# Mako_DSP_Audio_Codec.net
KiCad netlist of a schematic drawn in Altium Designer
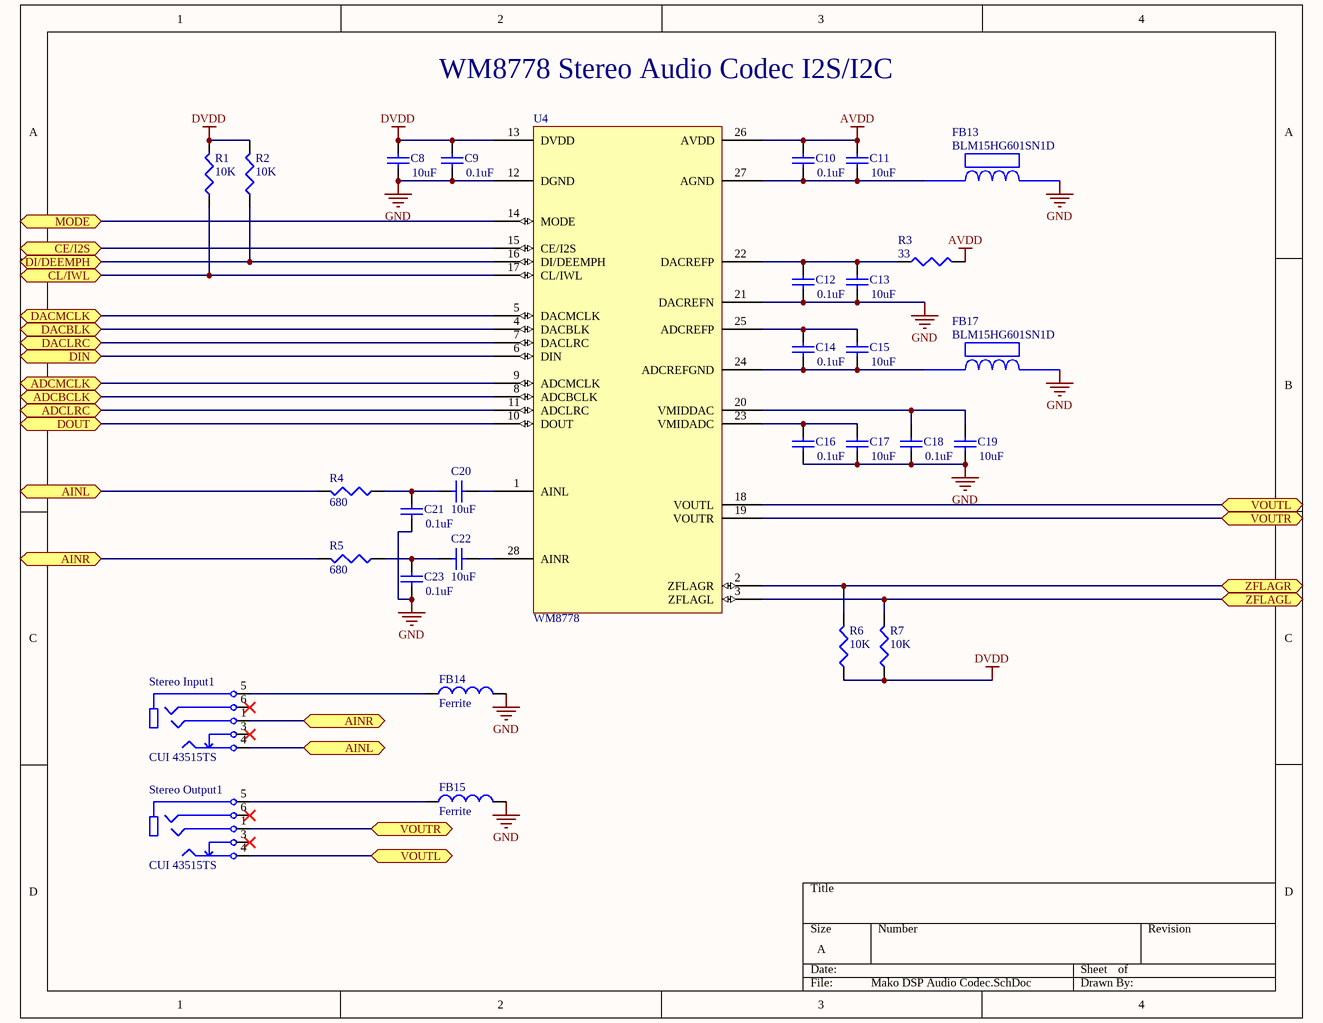
[diagram p0: Mako DSP Audio Codec.SchDoc]

(export (version "E")
  (design (tool "Eeschema 10.0.6"))
  (components
    (comp (ref "C8")
      (value "10uF")
      (footprint "1608[0603]")
      (description "Capacitor (Semiconductor SIM Model)")
      (fields (field (name "Comment") "Cap Semi") (field (name "PUBLISHER") "Altium Limited"))
      (libsource (lib "Miscellaneous Devices") (part "Cap Semi"))
    )
    (comp (ref "C9")
      (value "0.1uF")
      (footprint "1608[0603]")
      (description "Capacitor (Semiconductor SIM Model)")
      (fields (field (name "Comment") "Cap Semi") (field (name "PUBLISHER") "Altium Limited"))
      (libsource (lib "Miscellaneous Devices") (part "Cap Semi"))
    )
    (comp (ref "C10")
      (value "0.1uF")
      (footprint "1608[0603]")
      (description "Capacitor (Semiconductor SIM Model)")
      (fields (field (name "Comment") "Cap Semi") (field (name "PUBLISHER") "Altium Limited"))
      (libsource (lib "Miscellaneous Devices") (part "Cap Semi"))
    )
    (comp (ref "C11")
      (value "10uF")
      (footprint "1608[0603]")
      (description "Capacitor (Semiconductor SIM Model)")
      (fields (field (name "Comment") "Cap Semi") (field (name "PUBLISHER") "Altium Limited"))
      (libsource (lib "Miscellaneous Devices") (part "Cap Semi"))
    )
    (comp (ref "C12")
      (value "0.1uF")
      (footprint "1608[0603]")
      (description "Capacitor (Semiconductor SIM Model)")
      (fields (field (name "Comment") "Cap Semi") (field (name "PUBLISHER") "Altium Limited"))
      (libsource (lib "Miscellaneous Devices") (part "Cap Semi"))
    )
    (comp (ref "C13")
      (value "10uF")
      (footprint "1608[0603]")
      (description "Capacitor (Semiconductor SIM Model)")
      (fields (field (name "Comment") "Cap Semi") (field (name "PUBLISHER") "Altium Limited"))
      (libsource (lib "Miscellaneous Devices") (part "Cap Semi"))
    )
    (comp (ref "C14")
      (value "0.1uF")
      (footprint "1608[0603]")
      (description "Capacitor (Semiconductor SIM Model)")
      (fields (field (name "Comment") "Cap Semi") (field (name "PUBLISHER") "Altium Limited"))
      (libsource (lib "Miscellaneous Devices") (part "Cap Semi"))
    )
    (comp (ref "C15")
      (value "10uF")
      (footprint "1608[0603]")
      (description "Capacitor (Semiconductor SIM Model)")
      (fields (field (name "Comment") "Cap Semi") (field (name "PUBLISHER") "Altium Limited"))
      (libsource (lib "Miscellaneous Devices") (part "Cap Semi"))
    )
    (comp (ref "C16")
      (value "0.1uF")
      (footprint "1608[0603]")
      (description "Capacitor (Semiconductor SIM Model)")
      (fields (field (name "Comment") "Cap Semi") (field (name "PUBLISHER") "Altium Limited"))
      (libsource (lib "Miscellaneous Devices") (part "Cap Semi"))
    )
    (comp (ref "C17")
      (value "10uF")
      (footprint "1608[0603]")
      (description "Capacitor (Semiconductor SIM Model)")
      (fields (field (name "Comment") "Cap Semi") (field (name "PUBLISHER") "Altium Limited"))
      (libsource (lib "Miscellaneous Devices") (part "Cap Semi"))
    )
    (comp (ref "C18")
      (value "0.1uF")
      (footprint "1608[0603]")
      (description "Capacitor (Semiconductor SIM Model)")
      (fields (field (name "Comment") "Cap Semi") (field (name "PUBLISHER") "Altium Limited"))
      (libsource (lib "Miscellaneous Devices") (part "Cap Semi"))
    )
    (comp (ref "C19")
      (value "10uF")
      (footprint "1608[0603]")
      (description "Capacitor (Semiconductor SIM Model)")
      (fields (field (name "Comment") "Cap Semi") (field (name "PUBLISHER") "Altium Limited"))
      (libsource (lib "Miscellaneous Devices") (part "Cap Semi"))
    )
    (comp (ref "C20")
      (value "10uF")
      (footprint "Panasonic VS B")
      (description "Capacitor (Semiconductor SIM Model)")
      (fields (field (name "Comment") "Cap Semi") (field (name "PUBLISHER") "Altium Limited"))
      (libsource (lib "Miscellaneous Devices") (part "Cap Semi"))
    )
    (comp (ref "C21")
      (value "0.1uF")
      (footprint "SM 0805 - gap trimmed")
      (description "Capacitor (Semiconductor SIM Model)")
      (fields (field (name "Comment") "Cap Semi") (field (name "PUBLISHER") "Altium Limited"))
      (libsource (lib "Miscellaneous Devices") (part "Cap Semi"))
    )
    (comp (ref "C22")
      (value "10uF")
      (footprint "Panasonic VS B")
      (description "Capacitor (Semiconductor SIM Model)")
      (fields (field (name "Comment") "Cap Semi") (field (name "PUBLISHER") "Altium Limited"))
      (libsource (lib "Miscellaneous Devices") (part "Cap Semi"))
    )
    (comp (ref "C23")
      (value "0.1uF")
      (footprint "SM 0805 - gap trimmed")
      (description "Capacitor (Semiconductor SIM Model)")
      (fields (field (name "Comment") "Cap Semi") (field (name "PUBLISHER") "Altium Limited"))
      (libsource (lib "Miscellaneous Devices") (part "Cap Semi"))
    )
    (comp (ref "FB13")
      (value "BLM15HG601SN1D")
      (footprint "BLM18PG121SN1D")
      (libsource (lib "AHD Part Library") (part "BLM15HG601SN1D"))
    )
    (comp (ref "FB14")
      (value "Ferrite")
      (footprint "SM 0805 - gap trimmed")
      (description "Inductor")
      (fields (field (name "PUBLISHER") "Altium Limited"))
      (libsource (lib "Miscellaneous Devices") (part "Inductor"))
    )
    (comp (ref "FB15")
      (value "Ferrite")
      (footprint "SM 0805 - gap trimmed")
      (description "Inductor")
      (fields (field (name "PUBLISHER") "Altium Limited"))
      (libsource (lib "Miscellaneous Devices") (part "Inductor"))
    )
    (comp (ref "FB17")
      (value "BLM15HG601SN1D")
      (footprint "BLM18PG121SN1D")
      (libsource (lib "AHD Part Library") (part "BLM15HG601SN1D"))
    )
    (comp (ref "R1")
      (value "10K")
      (footprint "J1-0603")
      (description "Resistor")
      (fields (field (name "Comment") "Res3") (field (name "PUBLISHER") "Altium Limited"))
      (libsource (lib "Miscellaneous Devices") (part "Res3"))
    )
    (comp (ref "R2")
      (value "10K")
      (footprint "J1-0603")
      (description "Resistor")
      (fields (field (name "Comment") "Res3") (field (name "PUBLISHER") "Altium Limited"))
      (libsource (lib "Miscellaneous Devices") (part "Res3"))
    )
    (comp (ref "R3")
      (value "33")
      (footprint "J1-0603")
      (description "Resistor")
      (fields (field (name "Comment") "Res3") (field (name "PUBLISHER") "Altium Limited"))
      (libsource (lib "Miscellaneous Devices") (part "Res3"))
    )
    (comp (ref "R4")
      (value "680")
      (footprint "SM 0805 - gap trimmed")
      (description "Resistor")
      (fields (field (name "Comment") "Res3") (field (name "PUBLISHER") "Altium Limited"))
      (libsource (lib "Miscellaneous Devices") (part "Res3"))
    )
    (comp (ref "R5")
      (value "680")
      (footprint "SM 0805 - gap trimmed")
      (description "Resistor")
      (fields (field (name "Comment") "Res3") (field (name "PUBLISHER") "Altium Limited"))
      (libsource (lib "Miscellaneous Devices") (part "Res3"))
    )
    (comp (ref "R6")
      (value "10K")
      (footprint "J1-0603")
      (description "Resistor")
      (fields (field (name "Comment") "Res3") (field (name "PUBLISHER") "Altium Limited"))
      (libsource (lib "Miscellaneous Devices") (part "Res3"))
    )
    (comp (ref "R7")
      (value "10K")
      (footprint "J1-0603")
      (description "Resistor")
      (fields (field (name "Comment") "Res3") (field (name "PUBLISHER") "Altium Limited"))
      (libsource (lib "Miscellaneous Devices") (part "Res3"))
    )
    (comp (ref "Stereo Input1")
      (value "CUI 43515TS")
      (footprint "CUI SJ-43515TS")
      (libsource (lib "Adams Altium Library") (part "CUI 43515TS"))
    )
    (comp (ref "Stereo Output1")
      (value "CUI 43515TS")
      (footprint "CUI SJ-43515TS")
      (libsource (lib "Adams Altium Library") (part "CUI 43515TS"))
    )
    (comp (ref "U4")
      (value "WM8778")
      (footprint "WM8778")
      (libsource (lib "Mako DSP Schematic Library") (part "WM8778"))
    )
  )
  (nets
    (net (code "1") (name "/ADCBCLK") (class "Default")
      (node (ref "U4") (pin "8") (pinfunction "ADCBCLK_8") (pintype "bidirectional"))
    )
    (net (code "2") (name "/ADCLRC") (class "Default")
      (node (ref "U4") (pin "11") (pinfunction "ADCLRC_11") (pintype "bidirectional"))
    )
    (net (code "3") (name "/ADCMCLK") (class "Default")
      (node (ref "U4") (pin "9") (pinfunction "ADCMCLK_9") (pintype "bidirectional"))
    )
    (net (code "4") (name "/AINL") (class "Default")
      (node (ref "R4") (pin "2") (pinfunction "2_2") (pintype "passive"))
      (node (ref "Stereo Input1") (pin "4") (pinfunction "TIP_4") (pintype "passive"))
    )
    (net (code "5") (name "/AINR") (class "Default")
      (node (ref "R5") (pin "2") (pinfunction "2_2") (pintype "passive"))
      (node (ref "Stereo Input1") (pin "1") (pinfunction "R1_1") (pintype "passive"))
    )
    (net (code "6") (name "/CE{slash}I2S") (class "Default")
      (node (ref "U4") (pin "15") (pinfunction "CE/I2S_15") (pintype "bidirectional"))
    )
    (net (code "7") (name "/CL{slash}IWL") (class "Default")
      (node (ref "R1") (pin "1") (pinfunction "1_1") (pintype "passive"))
      (node (ref "U4") (pin "17") (pinfunction "CL/IWL_17") (pintype "bidirectional"))
    )
    (net (code "8") (name "/DACBLK") (class "Default")
      (node (ref "U4") (pin "4") (pinfunction "DACBLK_4") (pintype "bidirectional"))
    )
    (net (code "9") (name "/DACLRC") (class "Default")
      (node (ref "U4") (pin "7") (pinfunction "DACLRC_7") (pintype "bidirectional"))
    )
    (net (code "10") (name "/DACMCLK") (class "Default")
      (node (ref "U4") (pin "5") (pinfunction "DACMCLK_5") (pintype "bidirectional"))
    )
    (net (code "11") (name "/DIN") (class "Default")
      (node (ref "U4") (pin "6") (pinfunction "DIN_6") (pintype "bidirectional"))
    )
    (net (code "12") (name "/DI{slash}DEEMPH") (class "Default")
      (node (ref "R2") (pin "1") (pinfunction "1_1") (pintype "passive"))
      (node (ref "U4") (pin "16") (pinfunction "DI/DEEMPH_16") (pintype "bidirectional"))
    )
    (net (code "13") (name "/DOUT") (class "Default")
      (node (ref "U4") (pin "10") (pinfunction "DOUT_10") (pintype "bidirectional"))
    )
    (net (code "14") (name "/MODE") (class "Default")
      (node (ref "U4") (pin "14") (pinfunction "MODE_14") (pintype "bidirectional"))
    )
    (net (code "15") (name "/VOUTL") (class "Default")
      (node (ref "Stereo Output1") (pin "4") (pinfunction "TIP_4") (pintype "passive"))
      (node (ref "U4") (pin "18") (pinfunction "VOUTL_18") (pintype "passive"))
    )
    (net (code "16") (name "/VOUTR") (class "Default")
      (node (ref "Stereo Output1") (pin "1") (pinfunction "R1_1") (pintype "passive"))
      (node (ref "U4") (pin "19") (pinfunction "VOUTR_19") (pintype "passive"))
    )
    (net (code "17") (name "/ZFLAGL") (class "Default")
      (node (ref "R7") (pin "2") (pinfunction "2_2") (pintype "passive"))
      (node (ref "U4") (pin "3") (pinfunction "ZFLAGL_3") (pintype "bidirectional"))
    )
    (net (code "18") (name "/ZFLAGR") (class "Default")
      (node (ref "R6") (pin "2") (pinfunction "2_2") (pintype "passive"))
      (node (ref "U4") (pin "2") (pinfunction "ZFLAGR_2") (pintype "bidirectional"))
    )
    (net (code "19") (name "AVDD") (class "Default")
      (node (ref "C10") (pin "2") (pinfunction "2_2") (pintype "passive"))
      (node (ref "C11") (pin "2") (pinfunction "2_2") (pintype "passive"))
      (node (ref "R3") (pin "2") (pinfunction "2_2") (pintype "passive"))
      (node (ref "U4") (pin "26") (pinfunction "AVDD_26") (pintype "passive"))
    )
    (net (code "20") (name "DVDD") (class "Default")
      (node (ref "C8") (pin "2") (pinfunction "2_2") (pintype "passive"))
      (node (ref "C9") (pin "2") (pinfunction "2_2") (pintype "passive"))
      (node (ref "R1") (pin "2") (pinfunction "2_2") (pintype "passive"))
      (node (ref "R2") (pin "2") (pinfunction "2_2") (pintype "passive"))
      (node (ref "R6") (pin "1") (pinfunction "1_1") (pintype "passive"))
      (node (ref "R7") (pin "1") (pinfunction "1_1") (pintype "passive"))
      (node (ref "U4") (pin "13") (pinfunction "DVDD_13") (pintype "passive"))
    )
    (net (code "21") (name "GND") (class "Default")
      (node (ref "C12") (pin "1") (pinfunction "1_1") (pintype "passive"))
      (node (ref "C13") (pin "1") (pinfunction "1_1") (pintype "passive"))
      (node (ref "C16") (pin "1") (pinfunction "1_1") (pintype "passive"))
      (node (ref "C17") (pin "1") (pinfunction "1_1") (pintype "passive"))
      (node (ref "C18") (pin "1") (pinfunction "1_1") (pintype "passive"))
      (node (ref "C19") (pin "1") (pinfunction "1_1") (pintype "passive"))
      (node (ref "C21") (pin "1") (pinfunction "1_1") (pintype "passive"))
      (node (ref "C23") (pin "1") (pinfunction "1_1") (pintype "passive"))
      (node (ref "C8") (pin "1") (pinfunction "1_1") (pintype "passive"))
      (node (ref "C9") (pin "1") (pinfunction "1_1") (pintype "passive"))
      (node (ref "FB13") (pin "2") (pinfunction "2_2") (pintype "passive"))
      (node (ref "FB14") (pin "2") (pinfunction "2_2") (pintype "passive"))
      (node (ref "FB15") (pin "2") (pinfunction "2_2") (pintype "passive"))
      (node (ref "FB17") (pin "2") (pinfunction "2_2") (pintype "passive"))
      (node (ref "U4") (pin "12") (pinfunction "DGND_12") (pintype "passive"))
      (node (ref "U4") (pin "21") (pinfunction "DACREFN_21") (pintype "passive"))
    )
    (net (code "22") (name "Net-(C20-Pad2)") (class "Default")
      (node (ref "C20") (pin "2") (pinfunction "2_2") (pintype "passive"))
      (node (ref "C21") (pin "2") (pinfunction "2_2") (pintype "passive"))
      (node (ref "R4") (pin "1") (pinfunction "1_1") (pintype "passive"))
    )
    (net (code "23") (name "Net-(C22-Pad2)") (class "Default")
      (node (ref "C22") (pin "2") (pinfunction "2_2") (pintype "passive"))
      (node (ref "C23") (pin "2") (pinfunction "2_2") (pintype "passive"))
      (node (ref "R5") (pin "1") (pinfunction "1_1") (pintype "passive"))
    )
    (net (code "24") (name "Net-(Stereo Input1-SLEEVE)") (class "Default")
      (node (ref "FB14") (pin "1") (pinfunction "1_1") (pintype "passive"))
      (node (ref "Stereo Input1") (pin "5") (pinfunction "SLEEVE_5") (pintype "passive"))
    )
    (net (code "25") (name "Net-(Stereo Output1-SLEEVE)") (class "Default")
      (node (ref "FB15") (pin "1") (pinfunction "1_1") (pintype "passive"))
      (node (ref "Stereo Output1") (pin "5") (pinfunction "SLEEVE_5") (pintype "passive"))
    )
    (net (code "26") (name "Net-(U4-ADCREFGND)") (class "Default")
      (node (ref "C14") (pin "1") (pinfunction "1_1") (pintype "passive"))
      (node (ref "C15") (pin "1") (pinfunction "1_1") (pintype "passive"))
      (node (ref "FB17") (pin "1") (pinfunction "1_1") (pintype "passive"))
      (node (ref "U4") (pin "24") (pinfunction "ADCREFGND_24") (pintype "passive"))
    )
    (net (code "27") (name "Net-(U4-ADCREFP)") (class "Default")
      (node (ref "C14") (pin "2") (pinfunction "2_2") (pintype "passive"))
      (node (ref "C15") (pin "2") (pinfunction "2_2") (pintype "passive"))
      (node (ref "U4") (pin "25") (pinfunction "ADCREFP_25") (pintype "passive"))
    )
    (net (code "28") (name "Net-(U4-AGND)") (class "Default")
      (node (ref "C10") (pin "1") (pinfunction "1_1") (pintype "passive"))
      (node (ref "C11") (pin "1") (pinfunction "1_1") (pintype "passive"))
      (node (ref "FB13") (pin "1") (pinfunction "1_1") (pintype "passive"))
      (node (ref "U4") (pin "27") (pinfunction "AGND_27") (pintype "passive"))
    )
    (net (code "29") (name "Net-(U4-AINL)") (class "Default")
      (node (ref "C20") (pin "1") (pinfunction "1_1") (pintype "passive"))
      (node (ref "U4") (pin "1") (pinfunction "AINL_1") (pintype "passive"))
    )
    (net (code "30") (name "Net-(U4-AINR)") (class "Default")
      (node (ref "C22") (pin "1") (pinfunction "1_1") (pintype "passive"))
      (node (ref "U4") (pin "28") (pinfunction "AINR_28") (pintype "passive"))
    )
    (net (code "31") (name "Net-(U4-DACREFP)") (class "Default")
      (node (ref "C12") (pin "2") (pinfunction "2_2") (pintype "passive"))
      (node (ref "C13") (pin "2") (pinfunction "2_2") (pintype "passive"))
      (node (ref "R3") (pin "1") (pinfunction "1_1") (pintype "passive"))
      (node (ref "U4") (pin "22") (pinfunction "DACREFP_22") (pintype "passive"))
    )
    (net (code "32") (name "Net-(U4-VMIDADC)") (class "Default")
      (node (ref "C16") (pin "2") (pinfunction "2_2") (pintype "passive"))
      (node (ref "C17") (pin "2") (pinfunction "2_2") (pintype "passive"))
      (node (ref "U4") (pin "23") (pinfunction "VMIDADC_23") (pintype "passive"))
    )
    (net (code "33") (name "Net-(U4-VMIDDAC)") (class "Default")
      (node (ref "C18") (pin "2") (pinfunction "2_2") (pintype "passive"))
      (node (ref "C19") (pin "2") (pinfunction "2_2") (pintype "passive"))
      (node (ref "U4") (pin "20") (pinfunction "VMIDDAC_20") (pintype "passive"))
    )
    (net (code "34") (name "unconnected-(Stereo Input1-R2-Pad6)") (class "Default")
      (node (ref "Stereo Input1") (pin "6") (pinfunction "R2_6") (pintype "passive+no_connect"))
    )
    (net (code "35") (name "unconnected-(Stereo Input1-TS-Pad3)") (class "Default")
      (node (ref "Stereo Input1") (pin "3") (pinfunction "TS_3") (pintype "passive+no_connect"))
    )
    (net (code "36") (name "unconnected-(Stereo Output1-R2-Pad6)") (class "Default")
      (node (ref "Stereo Output1") (pin "6") (pinfunction "R2_6") (pintype "passive+no_connect"))
    )
    (net (code "37") (name "unconnected-(Stereo Output1-TS-Pad3)") (class "Default")
      (node (ref "Stereo Output1") (pin "3") (pinfunction "TS_3") (pintype "passive+no_connect"))
    )
  )
)
